# drive.net
KiCad netlist of a schematic drawn in Altium Designer
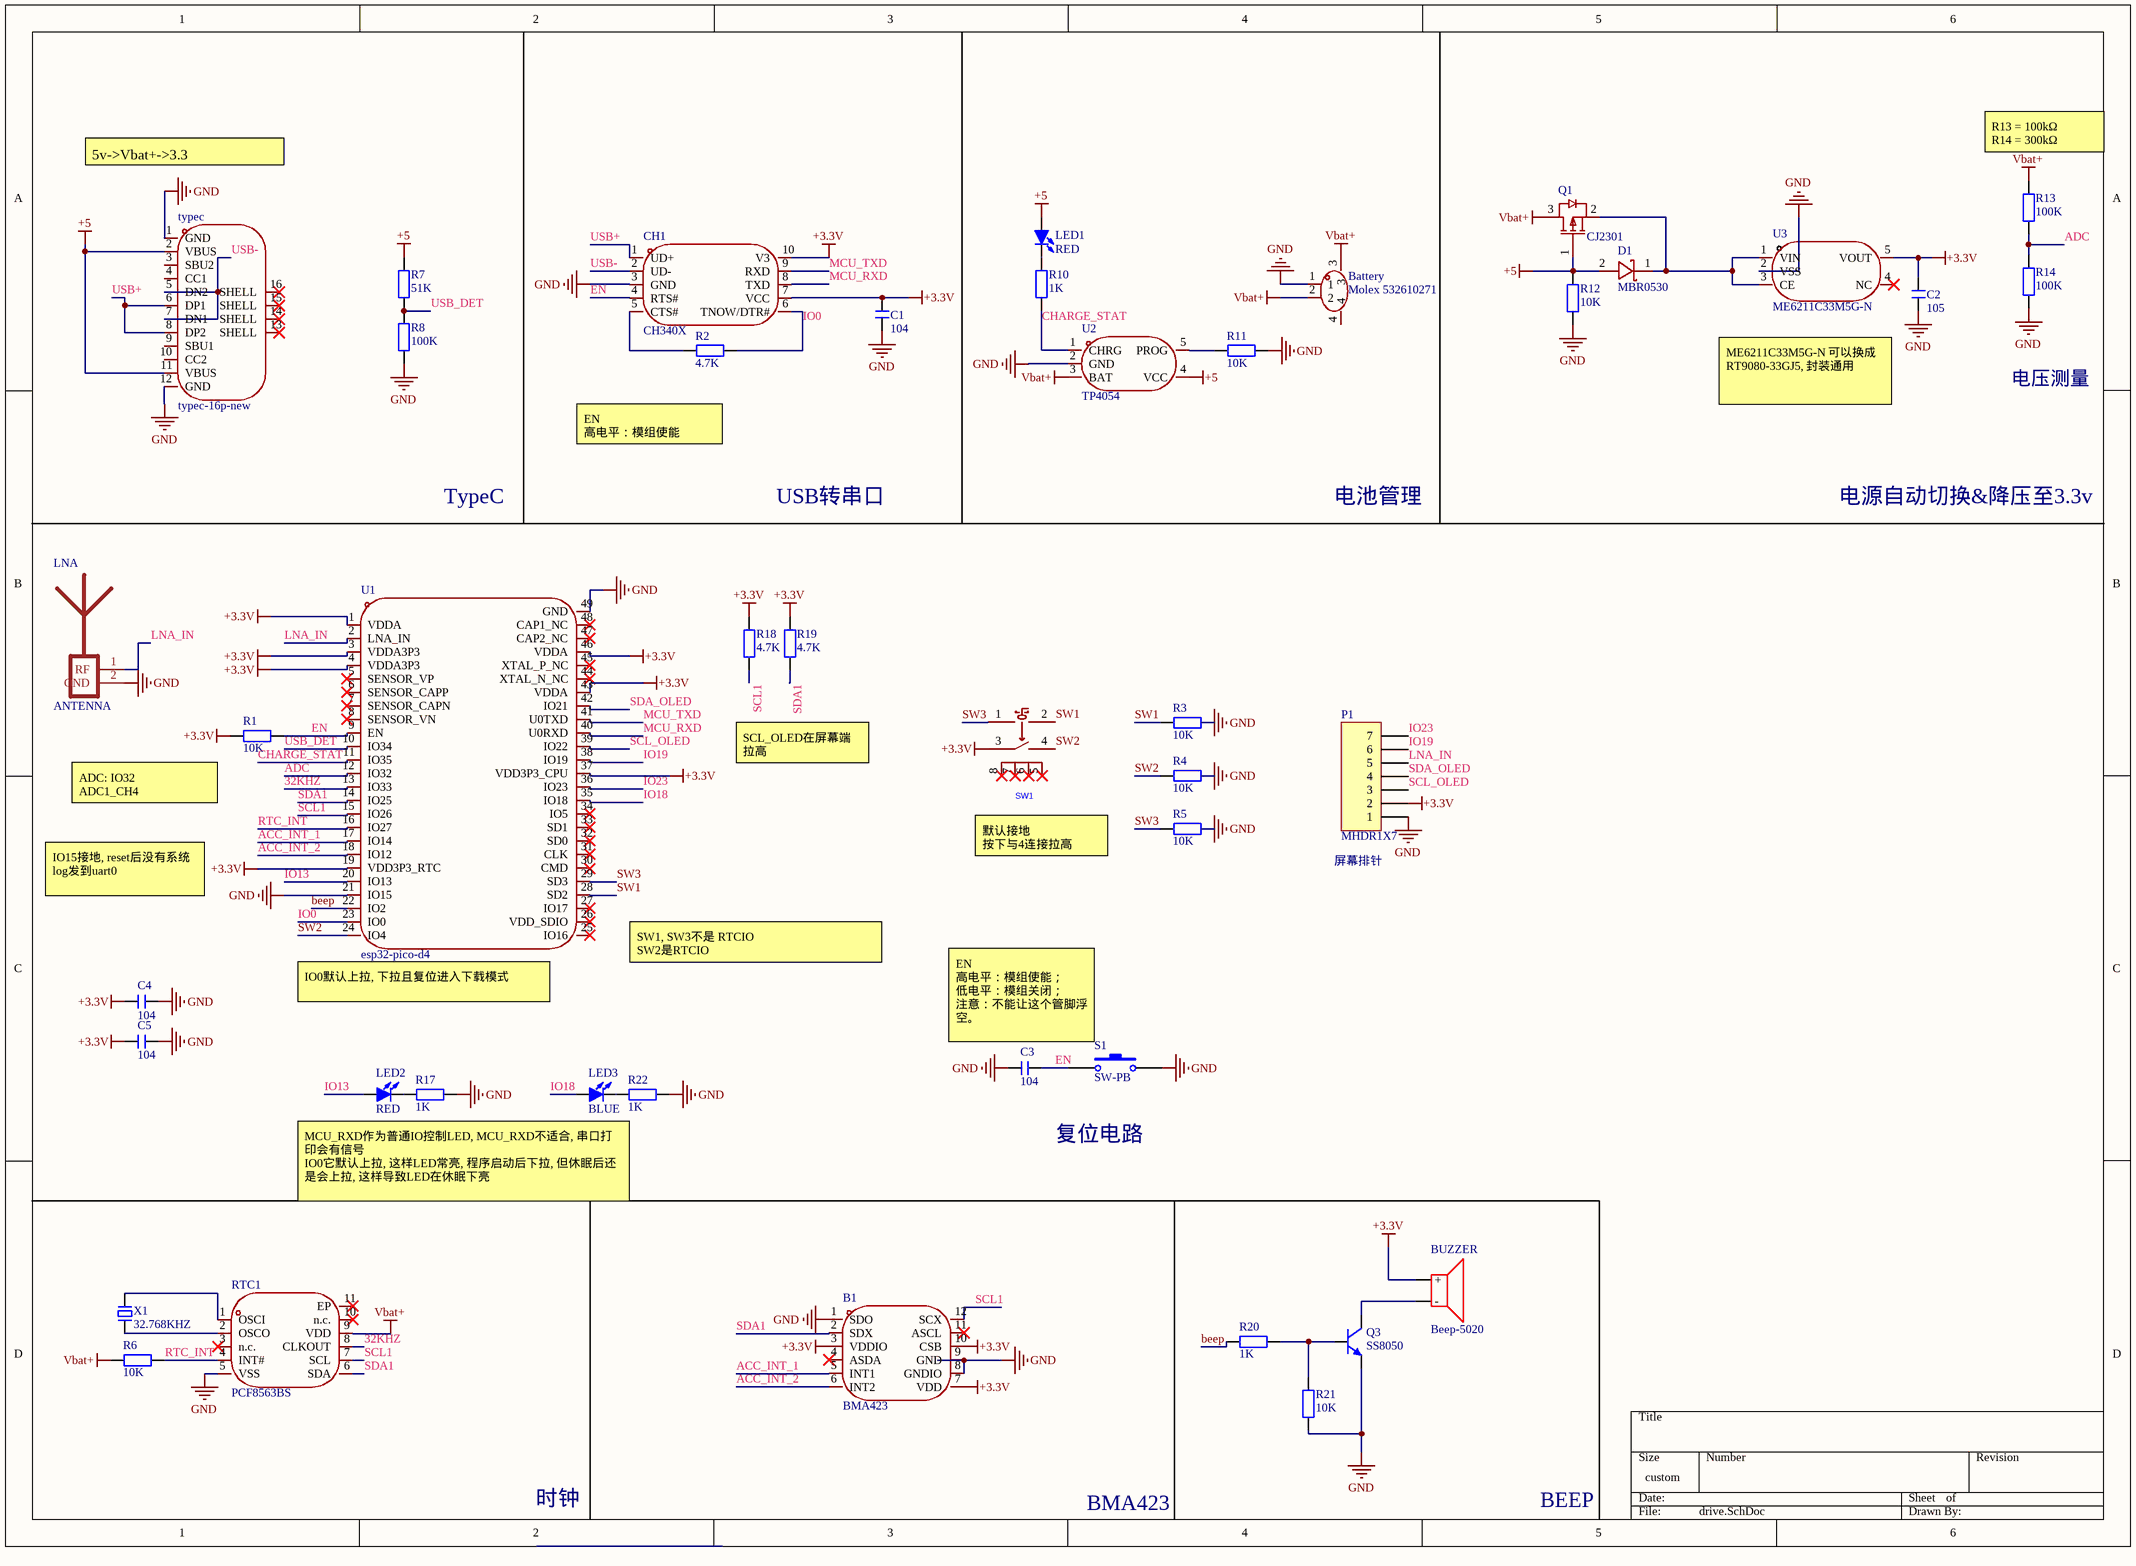
[diagram p0: drive.SchDoc]

(export (version "E")
  (design (tool "Eeschema 10.0.6"))
  (components
    (comp (ref "B1") (value "BMA423") (footprint "LGA-12(2x2)-2") (libsource (lib "Schlib1") (part "BMA423")))
    (comp (ref "Battery")
      (value "Molex 532610271")
      (footprint "SMD,P=1.25mm")
      (libsource (lib "Schlib1") (part "smd1.25"))
    )
    (comp (ref "BUZZER")
      (value "Beep-5020")
      (footprint "5020BUZZER")
      (description "贴片蜂鸣器5020最小封装")
      (libsource (lib "我的元件") (part "Beep-5020"))
    )
    (comp (ref "C1")
      (value "104")
      (footprint "C0402-min")
      (description "无极性贴片电容")
      (fields (field (name "版权归属") "源创客"))
      (libsource (lib "3.1   - 电阻-电容-电感") (part "C"))
    )
    (comp (ref "C2")
      (value "105")
      (footprint "C0402-min")
      (description "无极性贴片电容")
      (fields (field (name "版权归属") "源创客"))
      (libsource (lib "3.1   - 电阻-电容-电感") (part "C"))
    )
    (comp (ref "C3")
      (value "104")
      (footprint "C0402-min")
      (description "无极性贴片电容")
      (fields (field (name "版权归属") "源创客"))
      (libsource (lib "3.1   - 电阻-电容-电感") (part "C"))
    )
    (comp (ref "C4")
      (value "104")
      (footprint "C0402-min")
      (description "无极性贴片电容")
      (fields (field (name "版权归属") "源创客"))
      (libsource (lib "3.1   - 电阻-电容-电感") (part "C"))
    )
    (comp (ref "C5")
      (value "104")
      (footprint "C0402-min")
      (description "无极性贴片电容")
      (fields (field (name "版权归属") "源创客"))
      (libsource (lib "3.1   - 电阻-电容-电感") (part "C"))
    )
    (comp (ref "CH1") (value "CH340X") (footprint "MSOP-10") (libsource (lib "Schlib1") (part "CH340X")))
    (comp (ref "D1") (value "MBR0530") (footprint "SOD-123") (libsource (lib "Schlib1") (part "MBR0530T1G")))
    (comp (ref "LED1")
      (value "RED")
      (footprint "LED0402")
      (description "贴片LED")
      (fields (field (name "版权归属") "源创客"))
      (libsource (lib "9.1   - LED") (part "LED-SMD"))
    )
    (comp (ref "LED2")
      (value "RED")
      (footprint "LED0402")
      (description "贴片LED")
      (fields (field (name "版权归属") "源创客"))
      (libsource (lib "9.1   - LED") (part "LED-SMD"))
    )
    (comp (ref "LED3")
      (value "BLUE")
      (footprint "LED0402")
      (description "贴片LED")
      (fields (field (name "版权归属") "源创客"))
      (libsource (lib "9.1   - LED") (part "LED-SMD"))
    )
    (comp (ref "LNA") (value "ANTENNA") (footprint "SWRA117D") (libsource (lib "Schlib1") (part "ANTENNA")))
    (comp (ref "P1")
      (value "MHDR1X7")
      (footprint "MHDR1X7")
      (description "Header, 7-Pin")
      (fields (field (name "PUBLISHER") "Altium Limited"))
      (libsource (lib "Miscellaneous Connectors") (part "MHDR1X7"))
    )
    (comp (ref "Q1") (value "CJ2301") (footprint "SOT-23-3") (libsource (lib "Schlib1") (part "CJ2301")))
    (comp (ref "Q3")
      (value "SS8050")
      (footprint "SOT-23-3")
      (description "高频放大-NPN型")
      (fields (field (name "版权归属") "源创客"))
      (libsource (lib "6.2   - 三极管") (part "8050-SMD"))
    )
    (comp (ref "R1")
      (value "10K")
      (footprint "R0402")
      (description "贴片电阻")
      (fields (field (name "版权归属") "源创客"))
      (libsource (lib "3.1   - 电阻-电容-电感") (part "R"))
    )
    (comp (ref "R2")
      (value "4.7K")
      (footprint "R0402")
      (description "贴片电阻")
      (fields (field (name "版权归属") "源创客"))
      (libsource (lib "3.1   - 电阻-电容-电感") (part "R"))
    )
    (comp (ref "R3")
      (value "10K")
      (footprint "R0402")
      (description "贴片电阻")
      (fields (field (name "版权归属") "源创客"))
      (libsource (lib "3.1   - 电阻-电容-电感") (part "R"))
    )
    (comp (ref "R4")
      (value "10K")
      (footprint "R0402")
      (description "贴片电阻")
      (fields (field (name "版权归属") "源创客"))
      (libsource (lib "3.1   - 电阻-电容-电感") (part "R"))
    )
    (comp (ref "R5")
      (value "10K")
      (footprint "R0402")
      (description "贴片电阻")
      (fields (field (name "版权归属") "源创客"))
      (libsource (lib "3.1   - 电阻-电容-电感") (part "R"))
    )
    (comp (ref "R6")
      (value "10K")
      (footprint "R0402")
      (description "贴片电阻")
      (fields (field (name "版权归属") "源创客"))
      (libsource (lib "3.1   - 电阻-电容-电感") (part "R"))
    )
    (comp (ref "R7")
      (value "51K")
      (footprint "R0402")
      (description "贴片电阻")
      (fields (field (name "版权归属") "源创客"))
      (libsource (lib "3.1   - 电阻-电容-电感") (part "R"))
    )
    (comp (ref "R8")
      (value "100K")
      (footprint "R0402")
      (description "贴片电阻")
      (fields (field (name "版权归属") "源创客"))
      (libsource (lib "3.1   - 电阻-电容-电感") (part "R"))
    )
    (comp (ref "R10")
      (value "1K")
      (footprint "R0402")
      (description "贴片电阻")
      (fields (field (name "版权归属") "源创客"))
      (libsource (lib "3.1   - 电阻-电容-电感") (part "R"))
    )
    (comp (ref "R11")
      (value "10K")
      (footprint "R0402")
      (description "贴片电阻")
      (fields (field (name "版权归属") "源创客"))
      (libsource (lib "3.1   - 电阻-电容-电感") (part "R"))
    )
    (comp (ref "R12")
      (value "10K")
      (footprint "R0402")
      (description "贴片电阻")
      (fields (field (name "版权归属") "源创客"))
      (libsource (lib "3.1   - 电阻-电容-电感") (part "R"))
    )
    (comp (ref "R13")
      (value "100K")
      (footprint "R0402")
      (description "贴片电阻")
      (fields (field (name "版权归属") "源创客"))
      (libsource (lib "3.1   - 电阻-电容-电感") (part "R"))
    )
    (comp (ref "R14")
      (value "100K")
      (footprint "R0402")
      (description "贴片电阻")
      (fields (field (name "版权归属") "源创客"))
      (libsource (lib "3.1   - 电阻-电容-电感") (part "R"))
    )
    (comp (ref "R17")
      (value "1K")
      (footprint "R0402")
      (description "贴片电阻")
      (fields (field (name "版权归属") "源创客"))
      (libsource (lib "3.1   - 电阻-电容-电感") (part "R"))
    )
    (comp (ref "R18")
      (value "4.7K")
      (footprint "R0402")
      (description "贴片电阻")
      (fields (field (name "版权归属") "源创客"))
      (libsource (lib "3.1   - 电阻-电容-电感") (part "R"))
    )
    (comp (ref "R19")
      (value "4.7K")
      (footprint "R0402")
      (description "贴片电阻")
      (fields (field (name "版权归属") "源创客"))
      (libsource (lib "3.1   - 电阻-电容-电感") (part "R"))
    )
    (comp (ref "R20")
      (value "1K")
      (footprint "R0402")
      (description "贴片电阻")
      (fields (field (name "版权归属") "源创客"))
      (libsource (lib "3.1   - 电阻-电容-电感") (part "R"))
    )
    (comp (ref "R21")
      (value "10K")
      (footprint "R0402")
      (description "贴片电阻")
      (fields (field (name "版权归属") "源创客"))
      (libsource (lib "3.1   - 电阻-电容-电感") (part "R"))
    )
    (comp (ref "R22")
      (value "1K")
      (footprint "R0402")
      (description "贴片电阻")
      (fields (field (name "版权归属") "源创客"))
      (libsource (lib "3.1   - 电阻-电容-电感") (part "R"))
    )
    (comp (ref "RTC1")
      (value "PCF8563BS")
      (footprint "HVSON-10-EP(3x3)")
      (libsource (lib "Schlib1") (part "PCF8563BS"))
    )
    (comp (ref "S1")
      (value "SW-PB")
      (footprint "switch-2x3")
      (description "Switch")
      (fields (field (name "PUBLISHER") "Altium Limited"))
      (libsource (lib "Miscellaneous Devices") (part "SW-PB"))
    )
    (comp (ref "SW1")
      (value "TM-2024A")
      (footprint "LUNBO-min-out")
      (fields (field (name "MANUFACTURER") "XKB Connection(中国星坤)"))
      (libsource (lib "drive") (part "lunbo-min"))
    )
    (comp (ref "typec")
      (value "typec-16p-new")
      (footprint "type-c-16p-new")
      (libsource (lib "Schlib1") (part "typec-16p-new"))
    )
    (comp (ref "U1")
      (value "esp32-pico-d4")
      (footprint "QFN-48-EP(7x7)")
      (libsource (lib "Schlib1") (part "esp32-pico-d4"))
    )
    (comp (ref "U2") (value "TP4054") (footprint "SOT-23-5") (libsource (lib "Schlib1") (part "TP4054")))
    (comp (ref "U3")
      (value "ME6211C33M5G-N")
      (footprint "SOT-23-5")
      (libsource (lib "Schlib1") (part "ME6211C33M5G-N"))
    )
    (comp (ref "X1")
      (value "32.768KHZ")
      (footprint "SMD3215-2P")
      (description "2脚无源脚晶振")
      (fields (field (name "版权归属") "源创客"))
      (libsource (lib "10.1 - 保险丝-晶振") (part "XTAL-2P"))
    )
  )
  (nets
    (net (code "1") (name "+3.3V") (class "Default")
      (node (ref "B1") (pin "10") (pinfunction "CSB_10") (pintype "passive"))
      (node (ref "B1") (pin "3") (pinfunction "VDDIO_3") (pintype "passive"))
      (node (ref "B1") (pin "7") (pinfunction "VDD_7") (pintype "passive"))
      (node (ref "BUZZER") (pin "1") (pinfunction "+_1") (pintype "passive"))
      (node (ref "C1") (pin "2") (pinfunction "2_2") (pintype "passive"))
      (node (ref "C2") (pin "2") (pinfunction "2_2") (pintype "passive"))
      (node (ref "C4") (pin "2") (pinfunction "2_2") (pintype "passive"))
      (node (ref "C5") (pin "2") (pinfunction "2_2") (pintype "passive"))
      (node (ref "CH1") (pin "10") (pinfunction "V3_10") (pintype "passive"))
      (node (ref "CH1") (pin "7") (pinfunction "VCC_7") (pintype "passive"))
      (node (ref "P1") (pin "2") (pinfunction "2_2") (pintype "passive"))
      (node (ref "R1") (pin "1") (pinfunction "1_1") (pintype "passive"))
      (node (ref "R18") (pin "2") (pinfunction "2_2") (pintype "passive"))
      (node (ref "R19") (pin "2") (pinfunction "2_2") (pintype "passive"))
      (node (ref "SW1") (pin "3") (pinfunction "3_3") (pintype "passive"))
      (node (ref "U1") (pin "1") (pinfunction "VDDA_1") (pintype "passive"))
      (node (ref "U1") (pin "19") (pinfunction "VDD3P3_RTC_19") (pintype "passive"))
      (node (ref "U1") (pin "3") (pinfunction "VDDA3P3_3") (pintype "passive"))
      (node (ref "U1") (pin "37") (pinfunction "VDD3P3_CPU_37") (pintype "passive"))
      (node (ref "U1") (pin "4") (pinfunction "VDDA3P3_4") (pintype "passive"))
      (node (ref "U1") (pin "43") (pinfunction "VDDA_43") (pintype "passive"))
      (node (ref "U1") (pin "46") (pinfunction "VDDA_46") (pintype "passive"))
      (node (ref "U3") (pin "5") (pinfunction "VOUT_5") (pintype "passive"))
    )
    (net (code "2") (name "+5") (class "Default")
      (node (ref "D1") (pin "2") (pinfunction "A_2") (pintype "passive"))
      (node (ref "LED1") (pin "1") (pinfunction "A_1") (pintype "passive"))
      (node (ref "Q1") (pin "1") (pinfunction "G_1") (pintype "passive"))
      (node (ref "R12") (pin "2") (pinfunction "2_2") (pintype "passive"))
      (node (ref "R7") (pin "1") (pinfunction "1_1") (pintype "passive"))
      (node (ref "U2") (pin "4") (pinfunction "VCC_4") (pintype "passive"))
      (node (ref "typec") (pin "11") (pinfunction "VBUS_11") (pintype "passive"))
      (node (ref "typec") (pin "2") (pinfunction "VBUS_2") (pintype "passive"))
    )
    (net (code "3") (name "/32KHZ") (class "Default")
      (node (ref "RTC1") (pin "8") (pinfunction "CLKOUT_8") (pintype "passive"))
      (node (ref "U1") (pin "13") (pinfunction "IO33_13") (pintype "passive"))
    )
    (net (code "4") (name "/ACC_INT_1") (class "Default")
      (node (ref "B1") (pin "5") (pinfunction "INT1_5") (pintype "passive"))
      (node (ref "U1") (pin "17") (pinfunction "IO14_17") (pintype "passive"))
    )
    (net (code "5") (name "/ACC_INT_2") (class "Default")
      (node (ref "B1") (pin "6") (pinfunction "INT2_6") (pintype "passive"))
      (node (ref "U1") (pin "18") (pinfunction "IO12_18") (pintype "passive"))
    )
    (net (code "6") (name "/ADC") (class "Default")
      (node (ref "R13") (pin "1") (pinfunction "1_1") (pintype "passive"))
      (node (ref "R14") (pin "2") (pinfunction "2_2") (pintype "passive"))
      (node (ref "U1") (pin "12") (pinfunction "IO32_12") (pintype "passive"))
    )
    (net (code "7") (name "/CHARGE_STAT") (class "Default")
      (node (ref "R10") (pin "2") (pinfunction "2_2") (pintype "passive"))
      (node (ref "U1") (pin "11") (pinfunction "IO35_11") (pintype "passive"))
      (node (ref "U2") (pin "1") (pinfunction "CHRG_1") (pintype "passive"))
    )
    (net (code "8") (name "/EN") (class "Default")
      (node (ref "C3") (pin "2") (pinfunction "2_2") (pintype "passive"))
      (node (ref "CH1") (pin "4") (pinfunction "RTS#_4") (pintype "passive"))
      (node (ref "R1") (pin "2") (pinfunction "2_2") (pintype "passive"))
      (node (ref "S1") (pin "1") (pinfunction "1_1") (pintype "passive"))
      (node (ref "U1") (pin "9") (pinfunction "EN_9") (pintype "passive"))
    )
    (net (code "9") (name "/IO0") (class "Default")
      (node (ref "CH1") (pin "6") (pinfunction "TNOW/DTR#_6") (pintype "passive"))
      (node (ref "R2") (pin "1") (pinfunction "1_1") (pintype "passive"))
      (node (ref "U1") (pin "23") (pinfunction "IO0_23") (pintype "passive"))
    )
    (net (code "10") (name "/IO13") (class "Default")
      (node (ref "LED2") (pin "1") (pinfunction "A_1") (pintype "passive"))
      (node (ref "U1") (pin "20") (pinfunction "IO13_20") (pintype "passive"))
    )
    (net (code "11") (name "/IO18") (class "Default")
      (node (ref "LED3") (pin "1") (pinfunction "A_1") (pintype "passive"))
      (node (ref "U1") (pin "35") (pinfunction "IO18_35") (pintype "passive"))
    )
    (net (code "12") (name "/IO19") (class "Default")
      (node (ref "P1") (pin "6") (pinfunction "6_6") (pintype "passive"))
      (node (ref "U1") (pin "38") (pinfunction "IO19_38") (pintype "passive"))
    )
    (net (code "13") (name "/IO23") (class "Default")
      (node (ref "P1") (pin "7") (pinfunction "7_7") (pintype "passive"))
      (node (ref "U1") (pin "36") (pinfunction "IO23_36") (pintype "passive"))
    )
    (net (code "14") (name "/LNA_IN") (class "Default")
      (node (ref "LNA") (pin "1") (pinfunction "RF_1") (pintype "passive"))
      (node (ref "P1") (pin "5") (pinfunction "5_5") (pintype "passive"))
      (node (ref "U1") (pin "2") (pinfunction "LNA_IN_2") (pintype "passive"))
    )
    (net (code "15") (name "/MCU_RXD") (class "Default")
      (node (ref "CH1") (pin "8") (pinfunction "TXD_8") (pintype "passive"))
      (node (ref "U1") (pin "40") (pinfunction "U0RXD_40") (pintype "passive"))
    )
    (net (code "16") (name "/MCU_TXD") (class "Default")
      (node (ref "CH1") (pin "9") (pinfunction "RXD_9") (pintype "passive"))
      (node (ref "U1") (pin "41") (pinfunction "U0TXD_41") (pintype "passive"))
    )
    (net (code "17") (name "/RTC_INT") (class "Default")
      (node (ref "R6") (pin "2") (pinfunction "2_2") (pintype "passive"))
      (node (ref "RTC1") (pin "4") (pinfunction "INT#_4") (pintype "passive"))
      (node (ref "U1") (pin "16") (pinfunction "IO27_16") (pintype "passive"))
    )
    (net (code "18") (name "/SCL1") (class "Default")
      (node (ref "B1") (pin "12") (pinfunction "SCX_12") (pintype "passive"))
      (node (ref "R18") (pin "1") (pinfunction "1_1") (pintype "passive"))
      (node (ref "RTC1") (pin "7") (pinfunction "SCL_7") (pintype "passive"))
      (node (ref "U1") (pin "15") (pinfunction "IO26_15") (pintype "passive"))
    )
    (net (code "19") (name "/SCL_OLED") (class "Default")
      (node (ref "P1") (pin "3") (pinfunction "3_3") (pintype "passive"))
      (node (ref "U1") (pin "39") (pinfunction "IO22_39") (pintype "passive"))
    )
    (net (code "20") (name "/SDA1") (class "Default")
      (node (ref "B1") (pin "2") (pinfunction "SDX_2") (pintype "passive"))
      (node (ref "R19") (pin "1") (pinfunction "1_1") (pintype "passive"))
      (node (ref "RTC1") (pin "6") (pinfunction "SDA_6") (pintype "passive"))
      (node (ref "U1") (pin "14") (pinfunction "IO25_14") (pintype "passive"))
    )
    (net (code "21") (name "/SDA_OLED") (class "Default")
      (node (ref "P1") (pin "4") (pinfunction "4_4") (pintype "passive"))
      (node (ref "U1") (pin "42") (pinfunction "IO21_42") (pintype "passive"))
    )
    (net (code "22") (name "/SW1") (class "Default")
      (node (ref "R3") (pin "1") (pinfunction "1_1") (pintype "passive"))
      (node (ref "SW1") (pin "2") (pinfunction "2_2") (pintype "passive"))
      (node (ref "U1") (pin "28") (pinfunction "SD2_28") (pintype "passive"))
    )
    (net (code "23") (name "/SW2") (class "Default")
      (node (ref "R4") (pin "1") (pinfunction "1_1") (pintype "passive"))
      (node (ref "SW1") (pin "4") (pinfunction "4_4") (pintype "passive"))
      (node (ref "U1") (pin "24") (pinfunction "IO4_24") (pintype "passive"))
    )
    (net (code "24") (name "/SW3") (class "Default")
      (node (ref "R5") (pin "1") (pinfunction "1_1") (pintype "passive"))
      (node (ref "SW1") (pin "1") (pinfunction "1_1") (pintype "passive"))
      (node (ref "U1") (pin "29") (pinfunction "SD3_29") (pintype "passive"))
    )
    (net (code "25") (name "/USB+") (class "Default")
      (node (ref "CH1") (pin "1") (pinfunction "UD+_1") (pintype "passive"))
      (node (ref "typec") (pin "6") (pinfunction "DP1_6") (pintype "passive"))
      (node (ref "typec") (pin "8") (pinfunction "DP2_8") (pintype "passive"))
    )
    (net (code "26") (name "/USB-") (class "Default")
      (node (ref "CH1") (pin "2") (pinfunction "UD-_2") (pintype "passive"))
      (node (ref "typec") (pin "5") (pinfunction "DN2_5") (pintype "passive"))
      (node (ref "typec") (pin "7") (pinfunction "DN1_7") (pintype "passive"))
    )
    (net (code "27") (name "/USB_DET") (class "Default")
      (node (ref "R7") (pin "2") (pinfunction "2_2") (pintype "passive"))
      (node (ref "R8") (pin "1") (pinfunction "1_1") (pintype "passive"))
      (node (ref "U1") (pin "10") (pinfunction "IO34_10") (pintype "passive"))
    )
    (net (code "28") (name "/beep") (class "Default")
      (node (ref "R20") (pin "1") (pinfunction "1_1") (pintype "passive"))
      (node (ref "U1") (pin "22") (pinfunction "IO2_22") (pintype "passive"))
    )
    (net (code "29") (name "GND") (class "Default")
      (node (ref "B1") (pin "1") (pinfunction "SDO_1") (pintype "passive"))
      (node (ref "B1") (pin "8") (pinfunction "GNDIO_8") (pintype "passive"))
      (node (ref "B1") (pin "9") (pinfunction "GND_9") (pintype "passive"))
      (node (ref "Battery") (pin "1") (pinfunction "1_1") (pintype "passive"))
      (node (ref "C1") (pin "1") (pinfunction "1_1") (pintype "passive"))
      (node (ref "C2") (pin "1") (pinfunction "1_1") (pintype "passive"))
      (node (ref "C3") (pin "1") (pinfunction "1_1") (pintype "passive"))
      (node (ref "C4") (pin "1") (pinfunction "1_1") (pintype "passive"))
      (node (ref "C5") (pin "1") (pinfunction "1_1") (pintype "passive"))
      (node (ref "CH1") (pin "3") (pinfunction "GND_3") (pintype "passive"))
      (node (ref "LNA") (pin "2") (pinfunction "GND_2") (pintype "passive"))
      (node (ref "P1") (pin "1") (pinfunction "1_1") (pintype "passive"))
      (node (ref "Q3") (pin "2") (pinfunction "E_2") (pintype "passive"))
      (node (ref "R11") (pin "1") (pinfunction "1_1") (pintype "passive"))
      (node (ref "R12") (pin "1") (pinfunction "1_1") (pintype "passive"))
      (node (ref "R14") (pin "1") (pinfunction "1_1") (pintype "passive"))
      (node (ref "R17") (pin "2") (pinfunction "2_2") (pintype "passive"))
      (node (ref "R21") (pin "1") (pinfunction "1_1") (pintype "passive"))
      (node (ref "R22") (pin "2") (pinfunction "2_2") (pintype "passive"))
      (node (ref "R3") (pin "2") (pinfunction "2_2") (pintype "passive"))
      (node (ref "R4") (pin "2") (pinfunction "2_2") (pintype "passive"))
      (node (ref "R5") (pin "2") (pinfunction "2_2") (pintype "passive"))
      (node (ref "R8") (pin "2") (pinfunction "2_2") (pintype "passive"))
      (node (ref "RTC1") (pin "5") (pinfunction "VSS_5") (pintype "passive"))
      (node (ref "S1") (pin "2") (pinfunction "2_2") (pintype "passive"))
      (node (ref "U1") (pin "21") (pinfunction "IO15_21") (pintype "passive"))
      (node (ref "U1") (pin "49") (pinfunction "GND_49") (pintype "passive"))
      (node (ref "U2") (pin "2") (pinfunction "GND_2") (pintype "passive"))
      (node (ref "U3") (pin "2") (pinfunction "VSS_2") (pintype "passive"))
      (node (ref "typec") (pin "1") (pinfunction "GND_1") (pintype "passive"))
      (node (ref "typec") (pin "12") (pinfunction "GND_12") (pintype "passive"))
    )
    (net (code "30") (name "Net-(BUZZER--)") (class "Default")
      (node (ref "BUZZER") (pin "2") (pinfunction "-_2") (pintype "passive"))
      (node (ref "Q3") (pin "3") (pinfunction "C_3") (pintype "passive"))
    )
    (net (code "31") (name "Net-(CH1-CTS#)") (class "Default")
      (node (ref "CH1") (pin "5") (pinfunction "CTS#_5") (pintype "passive"))
      (node (ref "R2") (pin "2") (pinfunction "2_2") (pintype "passive"))
    )
    (net (code "32") (name "Net-(D1-C)") (class "Default")
      (node (ref "D1") (pin "1") (pinfunction "C_1") (pintype "passive"))
      (node (ref "Q1") (pin "2") (pinfunction "S_2") (pintype "passive"))
      (node (ref "U3") (pin "1") (pinfunction "VIN_1") (pintype "passive"))
      (node (ref "U3") (pin "3") (pinfunction "CE_3") (pintype "passive"))
    )
    (net (code "33") (name "Net-(LED1-K)") (class "Default")
      (node (ref "LED1") (pin "2") (pinfunction "K_2") (pintype "passive"))
      (node (ref "R10") (pin "1") (pinfunction "1_1") (pintype "passive"))
    )
    (net (code "34") (name "Net-(LED2-K)") (class "Default")
      (node (ref "LED2") (pin "2") (pinfunction "K_2") (pintype "passive"))
      (node (ref "R17") (pin "1") (pinfunction "1_1") (pintype "passive"))
    )
    (net (code "35") (name "Net-(LED3-K)") (class "Default")
      (node (ref "LED3") (pin "2") (pinfunction "K_2") (pintype "passive"))
      (node (ref "R22") (pin "1") (pinfunction "1_1") (pintype "passive"))
    )
    (net (code "36") (name "Net-(Q3-B)") (class "Default")
      (node (ref "Q3") (pin "1") (pinfunction "B_1") (pintype "passive"))
      (node (ref "R20") (pin "2") (pinfunction "2_2") (pintype "passive"))
      (node (ref "R21") (pin "2") (pinfunction "2_2") (pintype "passive"))
    )
    (net (code "37") (name "Net-(RTC1-OSCI)") (class "Default")
      (node (ref "RTC1") (pin "1") (pinfunction "OSCI_1") (pintype "passive"))
      (node (ref "X1") (pin "2") (pinfunction "2_2") (pintype "passive"))
    )
    (net (code "38") (name "Net-(RTC1-OSCO)") (class "Default")
      (node (ref "RTC1") (pin "2") (pinfunction "OSCO_2") (pintype "passive"))
      (node (ref "X1") (pin "1") (pinfunction "1_1") (pintype "passive"))
    )
    (net (code "39") (name "Net-(U2-PROG)") (class "Default")
      (node (ref "R11") (pin "2") (pinfunction "2_2") (pintype "passive"))
      (node (ref "U2") (pin "5") (pinfunction "PROG_5") (pintype "passive"))
    )
    (net (code "40") (name "Vbat+") (class "Default")
      (node (ref "Battery") (pin "2") (pinfunction "2_2") (pintype "passive"))
      (node (ref "Battery") (pin "3") (pinfunction "3_3") (pintype "passive"))
      (node (ref "Q1") (pin "3") (pinfunction "D_3") (pintype "passive"))
      (node (ref "R13") (pin "2") (pinfunction "2_2") (pintype "passive"))
      (node (ref "R6") (pin "1") (pinfunction "1_1") (pintype "passive"))
      (node (ref "RTC1") (pin "9") (pinfunction "VDD_9") (pintype "passive"))
      (node (ref "U2") (pin "3") (pinfunction "BAT_3") (pintype "passive"))
    )
    (net (code "41") (name "unconnected-(B1-ASCL-Pad11)") (class "Default")
      (node (ref "B1") (pin "11") (pinfunction "ASCL_11") (pintype "passive+no_connect"))
    )
    (net (code "42") (name "unconnected-(B1-ASDA-Pad4)") (class "Default")
      (node (ref "B1") (pin "4") (pinfunction "ASDA_4") (pintype "passive+no_connect"))
    )
    (net (code "43") (name "unconnected-(Battery-Pad4)") (class "Default")
      (node (ref "Battery") (pin "4") (pinfunction "4_4") (pintype "passive"))
    )
    (net (code "44") (name "unconnected-(RTC1-EP-Pad11)") (class "Default")
      (node (ref "RTC1") (pin "11") (pinfunction "EP_11") (pintype "passive+no_connect"))
    )
    (net (code "45") (name "unconnected-(RTC1-n.c.-Pad3)") (class "Default")
      (node (ref "RTC1") (pin "3") (pinfunction "n.c._3") (pintype "passive+no_connect"))
    )
    (net (code "46") (name "unconnected-(RTC1-n.c.-Pad10)") (class "Default")
      (node (ref "RTC1") (pin "10") (pinfunction "n.c._10") (pintype "passive+no_connect"))
    )
    (net (code "47") (name "unconnected-(SW1-Pad5)") (class "Default")
      (node (ref "SW1") (pin "5") (pinfunction "5_5") (pintype "passive+no_connect"))
    )
    (net (code "48") (name "unconnected-(SW1-Pad6)") (class "Default")
      (node (ref "SW1") (pin "6") (pinfunction "6_6") (pintype "passive+no_connect"))
    )
    (net (code "49") (name "unconnected-(SW1-Pad7)") (class "Default")
      (node (ref "SW1") (pin "7") (pinfunction "7_7") (pintype "passive+no_connect"))
    )
    (net (code "50") (name "unconnected-(SW1-Pad8)") (class "Default")
      (node (ref "SW1") (pin "8") (pinfunction "8_8") (pintype "passive+no_connect"))
    )
    (net (code "51") (name "unconnected-(U1-CAP1_NC-Pad48)") (class "Default")
      (node (ref "U1") (pin "48") (pinfunction "CAP1_NC_48") (pintype "passive+no_connect"))
    )
    (net (code "52") (name "unconnected-(U1-CAP2_NC-Pad47)") (class "Default")
      (node (ref "U1") (pin "47") (pinfunction "CAP2_NC_47") (pintype "passive+no_connect"))
    )
    (net (code "53") (name "unconnected-(U1-CLK-Pad31)") (class "Default")
      (node (ref "U1") (pin "31") (pinfunction "CLK_31") (pintype "passive+no_connect"))
    )
    (net (code "54") (name "unconnected-(U1-CMD-Pad30)") (class "Default")
      (node (ref "U1") (pin "30") (pinfunction "CMD_30") (pintype "passive"))
    )
    (net (code "55") (name "unconnected-(U1-IO5-Pad34)") (class "Default")
      (node (ref "U1") (pin "34") (pinfunction "IO5_34") (pintype "passive+no_connect"))
    )
    (net (code "56") (name "unconnected-(U1-IO16-Pad25)") (class "Default")
      (node (ref "U1") (pin "25") (pinfunction "IO16_25") (pintype "passive+no_connect"))
    )
    (net (code "57") (name "unconnected-(U1-IO17-Pad27)") (class "Default")
      (node (ref "U1") (pin "27") (pinfunction "IO17_27") (pintype "passive+no_connect"))
    )
    (net (code "58") (name "unconnected-(U1-SD0-Pad32)") (class "Default")
      (node (ref "U1") (pin "32") (pinfunction "SD0_32") (pintype "passive+no_connect"))
    )
    (net (code "59") (name "unconnected-(U1-SD1-Pad33)") (class "Default")
      (node (ref "U1") (pin "33") (pinfunction "SD1_33") (pintype "passive+no_connect"))
    )
    (net (code "60") (name "unconnected-(U1-SENSOR_CAPN-Pad7)") (class "Default")
      (node (ref "U1") (pin "7") (pinfunction "SENSOR_CAPN_7") (pintype "passive+no_connect"))
    )
    (net (code "61") (name "unconnected-(U1-SENSOR_CAPP-Pad6)") (class "Default")
      (node (ref "U1") (pin "6") (pinfunction "SENSOR_CAPP_6") (pintype "passive+no_connect"))
    )
    (net (code "62") (name "unconnected-(U1-SENSOR_VN-Pad8)") (class "Default")
      (node (ref "U1") (pin "8") (pinfunction "SENSOR_VN_8") (pintype "passive+no_connect"))
    )
    (net (code "63") (name "unconnected-(U1-SENSOR_VP-Pad5)") (class "Default")
      (node (ref "U1") (pin "5") (pinfunction "SENSOR_VP_5") (pintype "passive+no_connect"))
    )
    (net (code "64") (name "unconnected-(U1-VDD_SDIO-Pad26)") (class "Default")
      (node (ref "U1") (pin "26") (pinfunction "VDD_SDIO_26") (pintype "passive+no_connect"))
    )
    (net (code "65") (name "unconnected-(U1-XTAL_N_NC-Pad44)") (class "Default")
      (node (ref "U1") (pin "44") (pinfunction "XTAL_N_NC_44") (pintype "passive+no_connect"))
    )
    (net (code "66") (name "unconnected-(U1-XTAL_P_NC-Pad45)") (class "Default")
      (node (ref "U1") (pin "45") (pinfunction "XTAL_P_NC_45") (pintype "passive+no_connect"))
    )
    (net (code "67") (name "unconnected-(U3-NC-Pad4)") (class "Default")
      (node (ref "U3") (pin "4") (pinfunction "NC_4") (pintype "passive+no_connect"))
    )
    (net (code "68") (name "unconnected-(typec-CC1-Pad4)") (class "Default")
      (node (ref "typec") (pin "4") (pinfunction "CC1_4") (pintype "passive"))
    )
    (net (code "69") (name "unconnected-(typec-CC2-Pad10)") (class "Default")
      (node (ref "typec") (pin "10") (pinfunction "CC2_10") (pintype "passive"))
    )
    (net (code "70") (name "unconnected-(typec-SBU1-Pad9)") (class "Default")
      (node (ref "typec") (pin "9") (pinfunction "SBU1_9") (pintype "passive"))
    )
    (net (code "71") (name "unconnected-(typec-SBU2-Pad3)") (class "Default")
      (node (ref "typec") (pin "3") (pinfunction "SBU2_3") (pintype "passive"))
    )
    (net (code "72") (name "unconnected-(typec-SHELL-Pad13)") (class "Default")
      (node (ref "typec") (pin "13") (pinfunction "SHELL_13") (pintype "passive+no_connect"))
    )
    (net (code "73") (name "unconnected-(typec-SHELL-Pad14)") (class "Default")
      (node (ref "typec") (pin "14") (pinfunction "SHELL_14") (pintype "passive+no_connect"))
    )
    (net (code "74") (name "unconnected-(typec-SHELL-Pad15)") (class "Default")
      (node (ref "typec") (pin "15") (pinfunction "SHELL_15") (pintype "passive+no_connect"))
    )
    (net (code "75") (name "unconnected-(typec-SHELL-Pad16)") (class "Default")
      (node (ref "typec") (pin "16") (pinfunction "SHELL_16") (pintype "passive+no_connect"))
    )
  )
)
